# z80.net
KiCad netlist of a schematic drawn in EAGLE
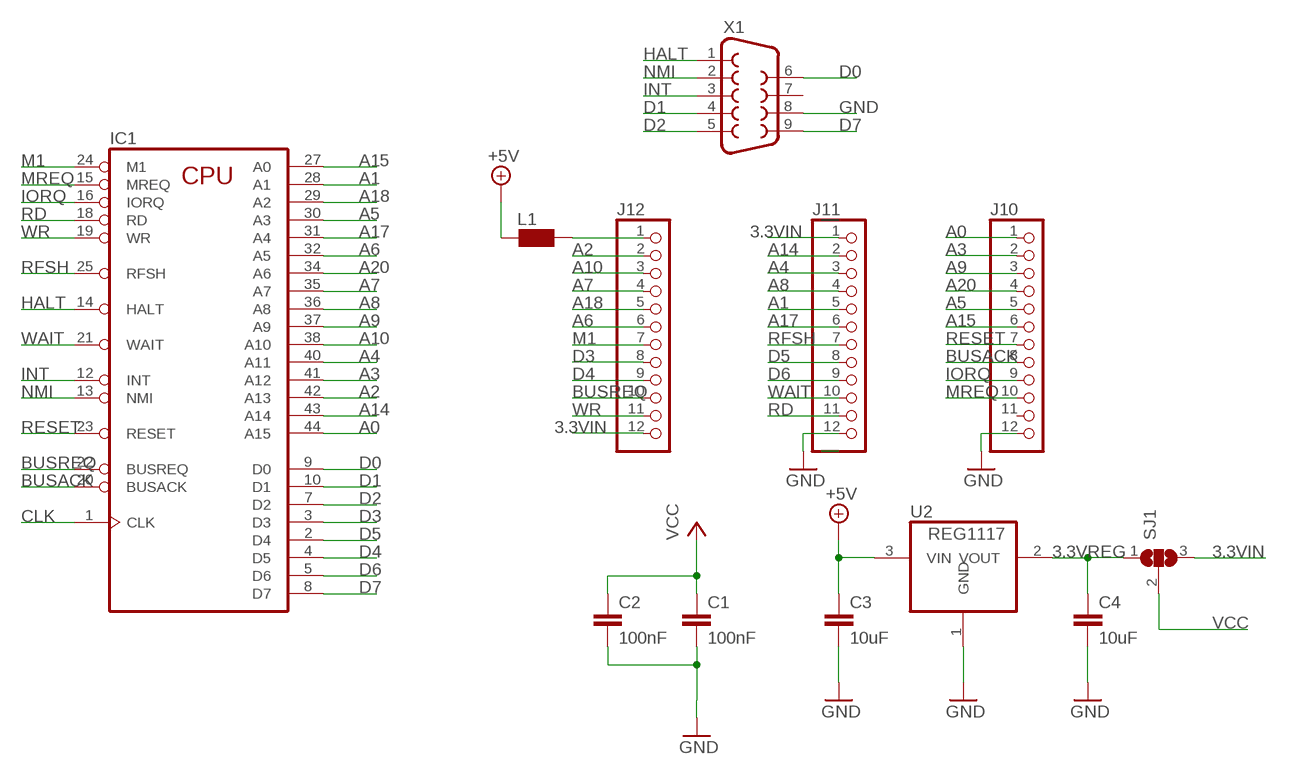
[diagram p0: schematic, sheet 1]

(export (version "E")
  (design (tool "Eeschema 10.0.6"))
  (components
    (comp (ref "C1")
      (value "100nF")
      (footprint "eagle-import:C0805K")
      (libsource (lib "eagle-import") (part "C-EUC0805K"))
    )
    (comp (ref "C2")
      (value "100nF")
      (footprint "eagle-import:C0805K")
      (libsource (lib "eagle-import") (part "C-EUC0805K"))
    )
    (comp (ref "C3")
      (value "10uF")
      (footprint "eagle-import:C0805K")
      (libsource (lib "eagle-import") (part "C-EUC0805K"))
    )
    (comp (ref "C4")
      (value "10uF")
      (footprint "eagle-import:C0805K")
      (libsource (lib "eagle-import") (part "C-EUC0805K"))
    )
    (comp (ref "IC1")
      (value "Z80CPU-F")
      (footprint "eagle-import:QFP-44")
      (libsource (lib "eagle-import") (part "Z80CPU-F"))
    )
    (comp (ref "J10")
      (value "PINHD-1X12")
      (footprint "eagle-import:1X12")
      (libsource (lib "eagle-import") (part "PINHD-1X12"))
    )
    (comp (ref "J11")
      (value "PINHD-1X12")
      (footprint "eagle-import:1X12")
      (libsource (lib "eagle-import") (part "PINHD-1X12"))
    )
    (comp (ref "J12")
      (value "PINHD-1X12")
      (footprint "eagle-import:1X12")
      (libsource (lib "eagle-import") (part "PINHD-1X12"))
    )
    (comp (ref "L1")
      (value "WE-CBF_0805")
      (footprint "eagle-import:0805")
      (libsource (lib "eagle-import") (part "WE-CBF_0805"))
    )
    (comp (ref "SJ1")
      (value "SJ2W")
      (footprint "eagle-import:SJ_2")
      (libsource (lib "eagle-import") (part "SJ2W"))
    )
    (comp (ref "U2")
      (value "REG1117")
      (footprint "eagle-import:SOT223")
      (libsource (lib "eagle-import") (part "REG1117"))
    )
    (comp (ref "X1")
      (value "F09D")
      (footprint "eagle-import:F09D")
      (libsource (lib "eagle-import") (part "F09D"))
    )
  )
  (nets
    (net (code "1") (name "+5V") (class "Default")
      (node (ref "C3") (pin "1") (pinfunction "1_1") (pintype "passive"))
      (node (ref "L1") (pin "2") (pinfunction "2_2") (pintype "passive"))
      (node (ref "U2") (pin "3") (pinfunction "VIN_3") (pintype "input"))
    )
    (net (code "2") (name "/3.3VIN") (class "Default")
      (node (ref "J11") (pin "1") (pinfunction "1_1") (pintype "passive"))
      (node (ref "J12") (pin "12") (pinfunction "12_12") (pintype "passive"))
      (node (ref "SJ1") (pin "3") (pinfunction "3_3") (pintype "passive"))
    )
    (net (code "3") (name "/3.3VREG") (class "Default")
      (node (ref "C4") (pin "1") (pinfunction "1_1") (pintype "passive"))
      (node (ref "SJ1") (pin "1") (pinfunction "1_1") (pintype "passive"))
      (node (ref "U2") (pin "2") (pinfunction "VOUT_2") (pintype "output"))
    )
    (net (code "4") (name "/A0") (class "Default")
      (node (ref "IC1") (pin "44") (pinfunction "A15_44") (pintype "output"))
      (node (ref "J10") (pin "1") (pinfunction "1_1") (pintype "passive"))
    )
    (net (code "5") (name "/A1") (class "Default")
      (node (ref "IC1") (pin "28") (pinfunction "A1_28") (pintype "output"))
      (node (ref "J11") (pin "5") (pinfunction "5_5") (pintype "passive"))
    )
    (net (code "6") (name "/A2") (class "Default")
      (node (ref "IC1") (pin "42") (pinfunction "A13_42") (pintype "output"))
      (node (ref "J12") (pin "2") (pinfunction "2_2") (pintype "passive"))
    )
    (net (code "7") (name "/A3") (class "Default")
      (node (ref "IC1") (pin "41") (pinfunction "A12_41") (pintype "output"))
      (node (ref "J10") (pin "2") (pinfunction "2_2") (pintype "passive"))
    )
    (net (code "8") (name "/A4") (class "Default")
      (node (ref "IC1") (pin "40") (pinfunction "A11_40") (pintype "output"))
      (node (ref "J11") (pin "3") (pinfunction "3_3") (pintype "passive"))
    )
    (net (code "9") (name "/A5") (class "Default")
      (node (ref "IC1") (pin "30") (pinfunction "A3_30") (pintype "output"))
      (node (ref "J10") (pin "5") (pinfunction "5_5") (pintype "passive"))
    )
    (net (code "10") (name "/A6") (class "Default")
      (node (ref "IC1") (pin "32") (pinfunction "A5_32") (pintype "output"))
      (node (ref "J12") (pin "6") (pinfunction "6_6") (pintype "passive"))
    )
    (net (code "11") (name "/A7") (class "Default")
      (node (ref "IC1") (pin "35") (pinfunction "A7_35") (pintype "output"))
      (node (ref "J12") (pin "4") (pinfunction "4_4") (pintype "passive"))
    )
    (net (code "12") (name "/A8") (class "Default")
      (node (ref "IC1") (pin "36") (pinfunction "A8_36") (pintype "output"))
      (node (ref "J11") (pin "4") (pinfunction "4_4") (pintype "passive"))
    )
    (net (code "13") (name "/A9") (class "Default")
      (node (ref "IC1") (pin "37") (pinfunction "A9_37") (pintype "output"))
      (node (ref "J10") (pin "3") (pinfunction "3_3") (pintype "passive"))
    )
    (net (code "14") (name "/A10") (class "Default")
      (node (ref "IC1") (pin "38") (pinfunction "A10_38") (pintype "output"))
      (node (ref "J12") (pin "3") (pinfunction "3_3") (pintype "passive"))
    )
    (net (code "15") (name "/A14") (class "Default")
      (node (ref "IC1") (pin "43") (pinfunction "A14_43") (pintype "output"))
      (node (ref "J11") (pin "2") (pinfunction "2_2") (pintype "passive"))
    )
    (net (code "16") (name "/A15") (class "Default")
      (node (ref "IC1") (pin "27") (pinfunction "A0_27") (pintype "output"))
      (node (ref "J10") (pin "6") (pinfunction "6_6") (pintype "passive"))
    )
    (net (code "17") (name "/A17") (class "Default")
      (node (ref "IC1") (pin "31") (pinfunction "A4_31") (pintype "output"))
      (node (ref "J11") (pin "6") (pinfunction "6_6") (pintype "passive"))
    )
    (net (code "18") (name "/A18") (class "Default")
      (node (ref "IC1") (pin "29") (pinfunction "A2_29") (pintype "output"))
      (node (ref "J12") (pin "5") (pinfunction "5_5") (pintype "passive"))
    )
    (net (code "19") (name "/A20") (class "Default")
      (node (ref "IC1") (pin "34") (pinfunction "A6_34") (pintype "output"))
      (node (ref "J10") (pin "4") (pinfunction "4_4") (pintype "passive"))
    )
    (net (code "20") (name "/BUSACK") (class "Default")
      (node (ref "IC1") (pin "20") (pinfunction "BUSACK_20") (pintype "output"))
      (node (ref "J10") (pin "8") (pinfunction "8_8") (pintype "passive"))
    )
    (net (code "21") (name "/BUSREQ") (class "Default")
      (node (ref "IC1") (pin "22") (pinfunction "BUSREQ_22") (pintype "input"))
      (node (ref "J12") (pin "10") (pinfunction "10_10") (pintype "passive"))
    )
    (net (code "22") (name "/CLK") (class "Default")
      (node (ref "IC1") (pin "1") (pinfunction "CLK_1") (pintype "input"))
    )
    (net (code "23") (name "/D0") (class "Default")
      (node (ref "IC1") (pin "9") (pinfunction "D0_9") (pintype "bidirectional"))
      (node (ref "X1") (pin "6") (pinfunction "6_6") (pintype "passive"))
    )
    (net (code "24") (name "/D1") (class "Default")
      (node (ref "IC1") (pin "10") (pinfunction "D1_10") (pintype "bidirectional"))
      (node (ref "X1") (pin "4") (pinfunction "4_4") (pintype "passive"))
    )
    (net (code "25") (name "/D2") (class "Default")
      (node (ref "IC1") (pin "7") (pinfunction "D2_7") (pintype "bidirectional"))
      (node (ref "X1") (pin "5") (pinfunction "5_5") (pintype "passive"))
    )
    (net (code "26") (name "/D3") (class "Default")
      (node (ref "IC1") (pin "3") (pinfunction "D3_3") (pintype "bidirectional"))
      (node (ref "J12") (pin "8") (pinfunction "8_8") (pintype "passive"))
    )
    (net (code "27") (name "/D4") (class "Default")
      (node (ref "IC1") (pin "4") (pinfunction "D5_4") (pintype "bidirectional"))
      (node (ref "J12") (pin "9") (pinfunction "9_9") (pintype "passive"))
    )
    (net (code "28") (name "/D5") (class "Default")
      (node (ref "IC1") (pin "2") (pinfunction "D4_2") (pintype "bidirectional"))
      (node (ref "J11") (pin "8") (pinfunction "8_8") (pintype "passive"))
    )
    (net (code "29") (name "/D6") (class "Default")
      (node (ref "IC1") (pin "5") (pinfunction "D6_5") (pintype "bidirectional"))
      (node (ref "J11") (pin "9") (pinfunction "9_9") (pintype "passive"))
    )
    (net (code "30") (name "/D7") (class "Default")
      (node (ref "IC1") (pin "8") (pinfunction "D7_8") (pintype "bidirectional"))
      (node (ref "X1") (pin "9") (pinfunction "9_9") (pintype "passive"))
    )
    (net (code "31") (name "/HALT") (class "Default")
      (node (ref "IC1") (pin "14") (pinfunction "HALT_14") (pintype "output"))
      (node (ref "X1") (pin "1") (pinfunction "1_1") (pintype "passive"))
    )
    (net (code "32") (name "/INT") (class "Default")
      (node (ref "IC1") (pin "12") (pinfunction "INT_12") (pintype "input"))
      (node (ref "X1") (pin "3") (pinfunction "3_3") (pintype "passive"))
    )
    (net (code "33") (name "/IORQ") (class "Default")
      (node (ref "IC1") (pin "16") (pinfunction "IORQ_16") (pintype "output"))
      (node (ref "J10") (pin "9") (pinfunction "9_9") (pintype "passive"))
    )
    (net (code "34") (name "/M1") (class "Default")
      (node (ref "IC1") (pin "24") (pinfunction "M1_24") (pintype "output"))
      (node (ref "J12") (pin "7") (pinfunction "7_7") (pintype "passive"))
    )
    (net (code "35") (name "/MREQ") (class "Default")
      (node (ref "IC1") (pin "15") (pinfunction "MREQ_15") (pintype "output"))
      (node (ref "J10") (pin "10") (pinfunction "10_10") (pintype "passive"))
    )
    (net (code "36") (name "/NMI") (class "Default")
      (node (ref "IC1") (pin "13") (pinfunction "NMI_13") (pintype "input"))
      (node (ref "X1") (pin "2") (pinfunction "2_2") (pintype "passive"))
    )
    (net (code "37") (name "/RD") (class "Default")
      (node (ref "IC1") (pin "18") (pinfunction "RD_18") (pintype "output"))
      (node (ref "J11") (pin "11") (pinfunction "11_11") (pintype "passive"))
    )
    (net (code "38") (name "/RESET") (class "Default")
      (node (ref "IC1") (pin "23") (pinfunction "RESET_23") (pintype "input"))
      (node (ref "J10") (pin "7") (pinfunction "7_7") (pintype "passive"))
    )
    (net (code "39") (name "/RFSH") (class "Default")
      (node (ref "IC1") (pin "25") (pinfunction "RFSH_25") (pintype "output"))
      (node (ref "J11") (pin "7") (pinfunction "7_7") (pintype "passive"))
    )
    (net (code "40") (name "/WAIT") (class "Default")
      (node (ref "IC1") (pin "21") (pinfunction "WAIT_21") (pintype "input"))
      (node (ref "J11") (pin "10") (pinfunction "10_10") (pintype "passive"))
    )
    (net (code "41") (name "/WR") (class "Default")
      (node (ref "IC1") (pin "19") (pinfunction "WR_19") (pintype "output"))
      (node (ref "J12") (pin "11") (pinfunction "11_11") (pintype "passive"))
    )
    (net (code "42") (name "GND") (class "Default")
      (node (ref "C1") (pin "2") (pinfunction "2_2") (pintype "passive"))
      (node (ref "C2") (pin "2") (pinfunction "2_2") (pintype "passive"))
      (node (ref "C3") (pin "2") (pinfunction "2_2") (pintype "passive"))
      (node (ref "C4") (pin "2") (pinfunction "2_2") (pintype "passive"))
      (node (ref "J10") (pin "12") (pinfunction "12_12") (pintype "passive"))
      (node (ref "J11") (pin "12") (pinfunction "12_12") (pintype "passive"))
      (node (ref "U2") (pin "1") (pinfunction "GND_1") (pintype "power_in"))
      (node (ref "X1") (pin "8") (pinfunction "8_8") (pintype "passive"))
    )
    (net (code "43") (name "Net-(J12-Pad1)") (class "Default")
      (node (ref "J12") (pin "1") (pinfunction "1_1") (pintype "passive"))
      (node (ref "L1") (pin "1") (pinfunction "1_1") (pintype "passive"))
    )
    (net (code "44") (name "VCC") (class "Default")
      (node (ref "C1") (pin "1") (pinfunction "1_1") (pintype "passive"))
      (node (ref "C2") (pin "1") (pinfunction "1_1") (pintype "passive"))
      (node (ref "SJ1") (pin "2") (pinfunction "2_2") (pintype "passive"))
    )
    (net (code "45") (name "unconnected-(J10-Pad11)") (class "Default")
      (node (ref "J10") (pin "11") (pinfunction "11_11") (pintype "passive"))
    )
    (net (code "46") (name "unconnected-(X1-Pad7)") (class "Default")
      (node (ref "X1") (pin "7") (pinfunction "7_7") (pintype "passive"))
    )
  )
)
